# Page1.net
KiCad netlist of a schematic drawn in Altium Designer
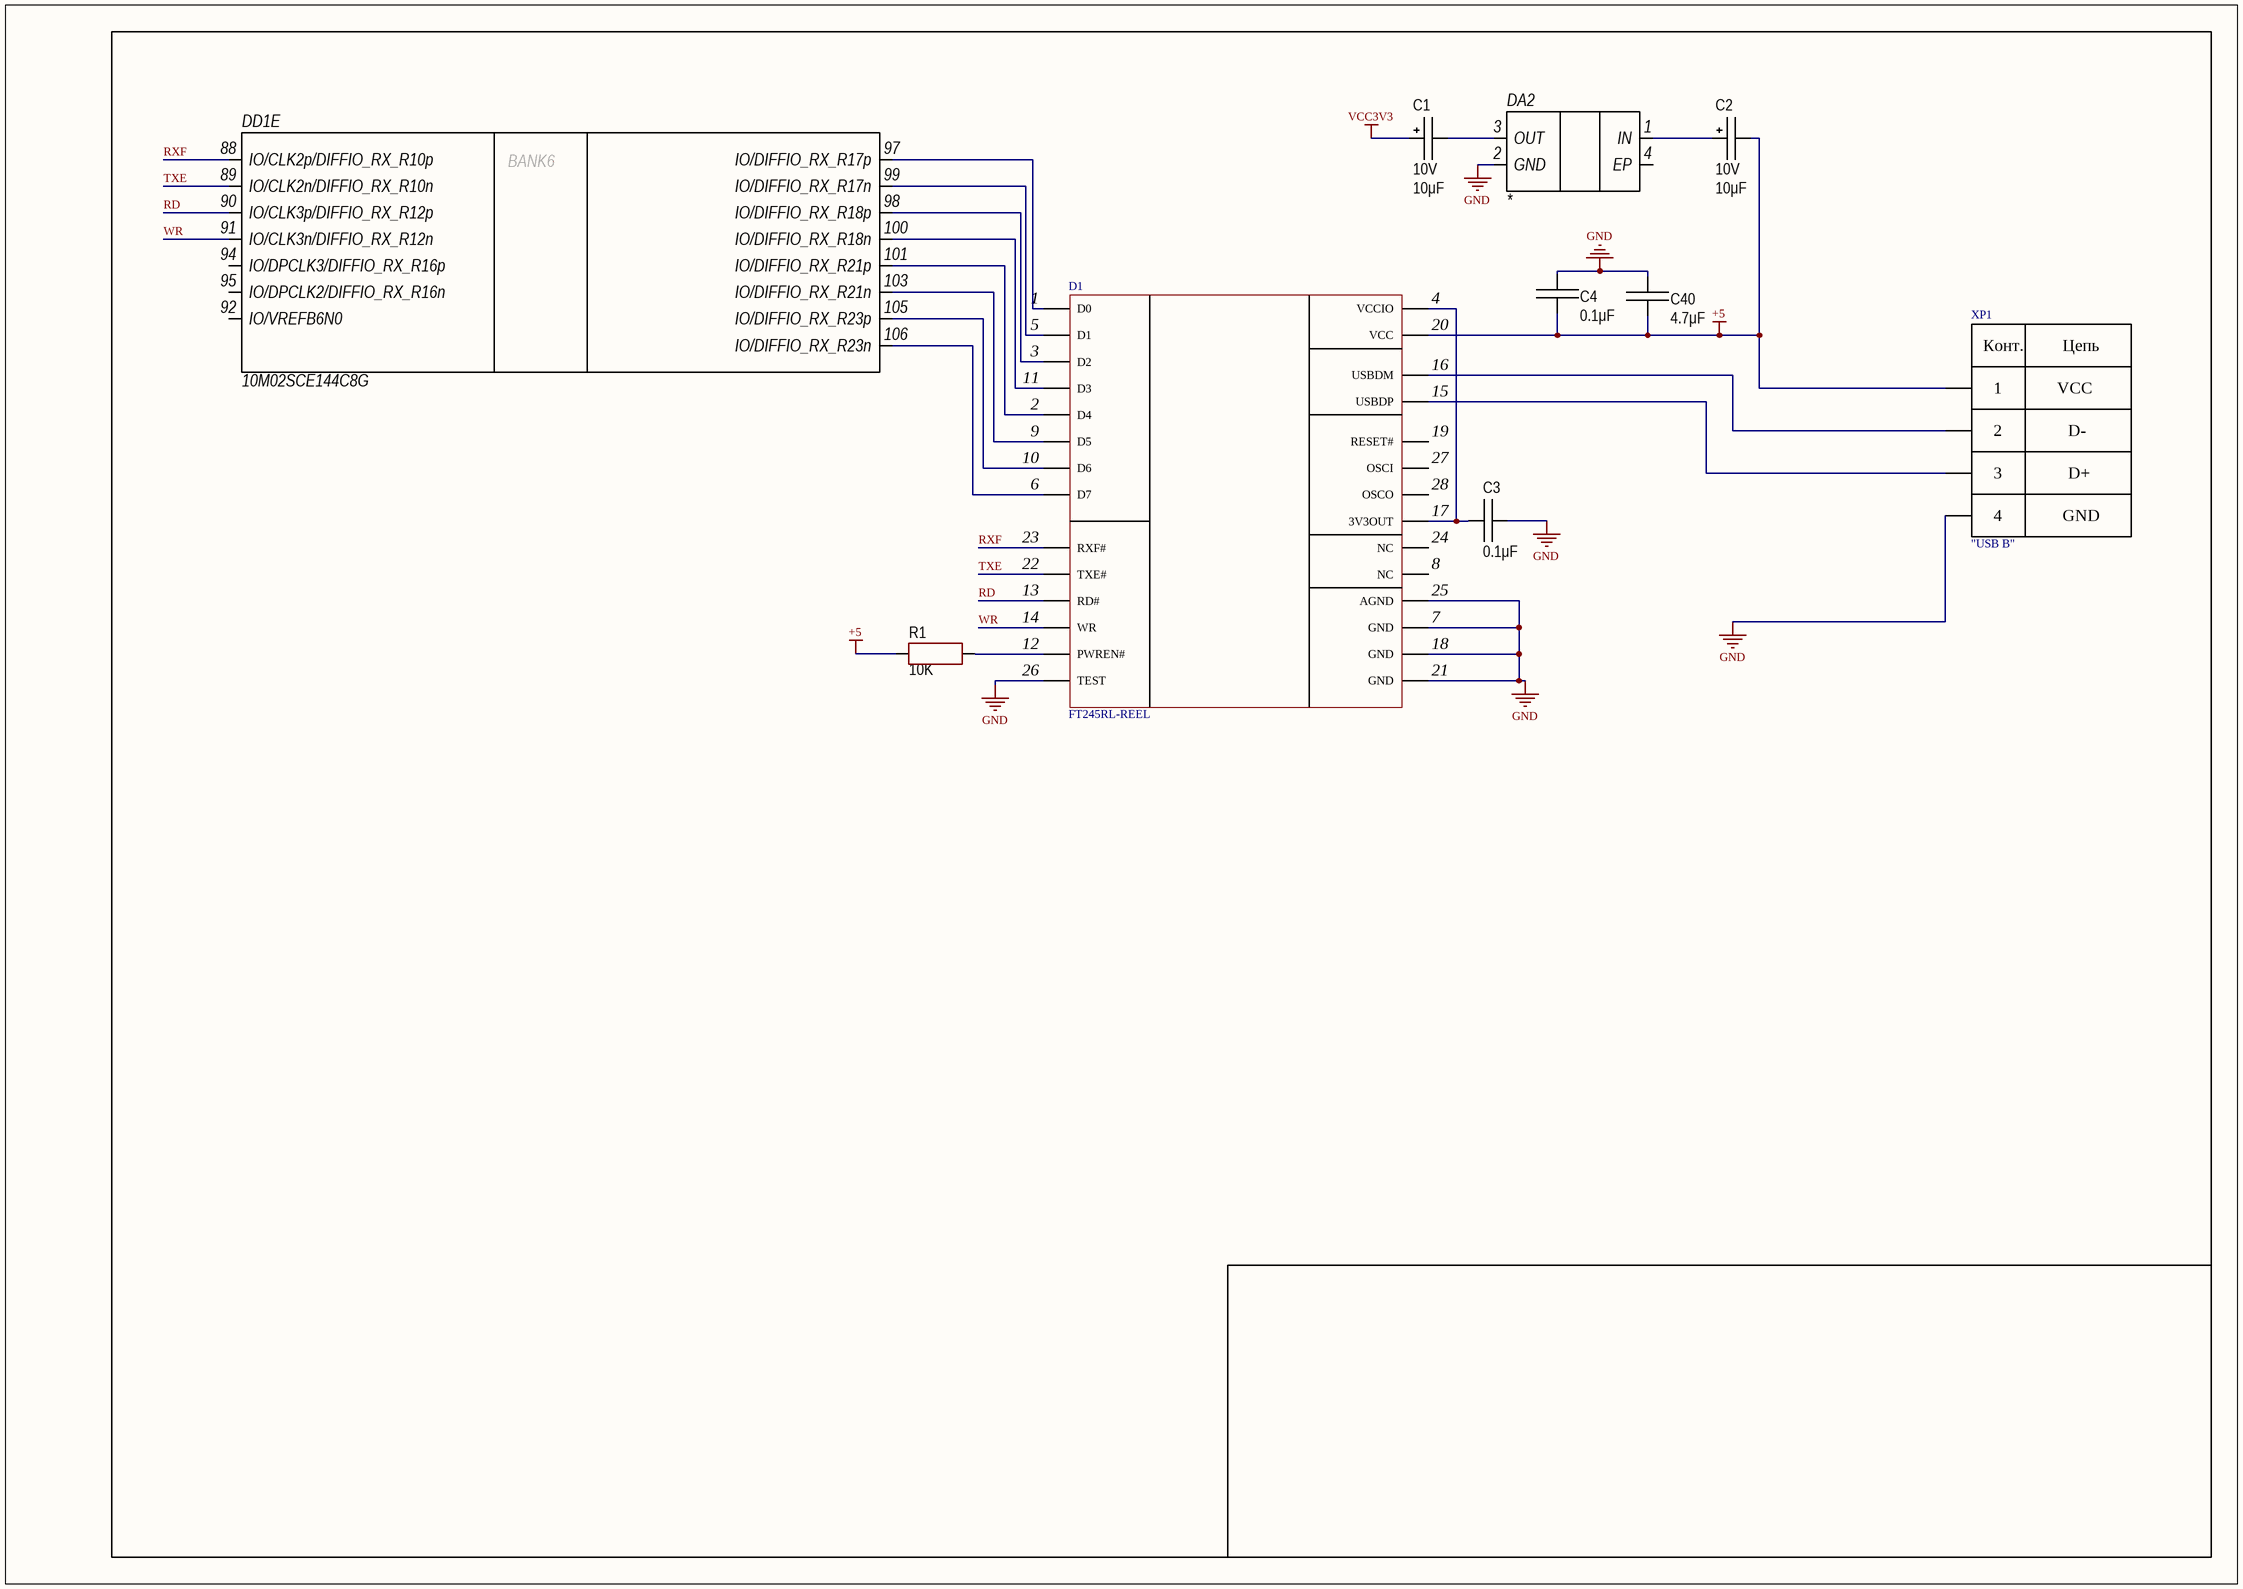
[diagram p0: Page1.SchDoc]

(export (version "E")
  (design (tool "Eeschema 10.0.6"))
  (components
    (comp (ref "C1")
      (value "10μF")
      (footprint "CAP: TANTAL-A")
      (fields
        (field (name "PARTNUMBER") "F930J107KAAAJ6")
        (field (name "VALUEMANUFACTURERPARTNUMBER") "Tantalum capacitor, 10μF, 10V, ±10%, 2Ohm, case A (3216), -55...+85°C")
        (field (name "TOLERANCE") "±10%")
        (field (name "VOLTAGE") "10V")
      )
      (libsource (lib "Capacitor") (part "Tantal_A"))
    )
    (comp (ref "C2")
      (value "10μF")
      (footprint "CAP: TANTAL-A")
      (fields
        (field (name "PARTNUMBER") "F930J107KAAAJ6")
        (field (name "VALUEMANUFACTURERPARTNUMBER") "Tantalum capacitor, 10μF, 10V, ±10%, 2Ohm, case A (3216), -55...+85°C")
        (field (name "TOLERANCE") "±10%")
        (field (name "VOLTAGE") "10V")
      )
      (libsource (lib "Capacitor") (part "Tantal_A"))
    )
    (comp (ref "C3")
      (value "0.1μF")
      (footprint "CAP: 0805")
      (fields
        (field (name "MANUFACTURER") "Yageo")
        (field (name "PARTNUMBER") "CC0805KRX7R7BB104")
        (field (name "VALUEMANUFACTURERPARTNUMBER") "Ceramic capacitor, 0.1μF, X7R, ±10%, , 0805, -55...+125°C")
      )
      (libsource (lib "Capacitor") (part "Ceramic_0805"))
    )
    (comp (ref "C4")
      (value "0.1μF")
      (footprint "CAP: 0805")
      (fields
        (field (name "MANUFACTURER") "Yageo")
        (field (name "PARTNUMBER") "CC0805KRX7R7BB104")
        (field (name "VALUEMANUFACTURERPARTNUMBER") "Ceramic capacitor, 0.1μF, X7R, ±10%, , 0805, -55...+125°C")
      )
      (libsource (lib "Capacitor") (part "Ceramic_0805"))
    )
    (comp (ref "C40")
      (value "4.7μF")
      (footprint "CAP: 0805")
      (fields
        (field (name "MANUFACTURER") "Yageo")
        (field (name "PARTNUMBER") "CC0805KRX7R7BB104")
        (field (name "VALUEMANUFACTURERPARTNUMBER") "Ceramic capacitor, 4.7μF, X7R, ±10%, , 0805, -55...+125°C")
      )
      (libsource (lib "Capacitor") (part "Ceramic_0805"))
    )
    (comp (ref "D1")
      (value "FT245RL-REEL")
      (footprint "28-SSOP")
      (description "IC USB TO PARALLEL FIFO 28-SSOP")
      (libsource (lib "Integrated_Library") (part "FT245RL-REEL"))
    )
    (comp (ref "DA2")
      (value "*")
      (footprint "SOT-223")
      (description "Voltage Regulator")
      (fields (field (name "PARTNUMBER") "MIC5233-3.3YS"))
      (libsource (lib "Integrated_Library") (part "MIC5233"))
    )
    (comp (ref "DD1")
      (value "10M02SCE144C8G")
      (footprint "144-Lead EQFP")
      (description "MAX10 FPGA")
      (fields (field (name "MANUFACTURER") "Intel"))
      (libsource (lib "Integrated_Library") (part "10M02SCE144C8G"))
    )
    (comp (ref "R1")
      (value "10K")
      (footprint "RES: 0805")
      (fields
        (field (name "MANUFACTURER") "Yageo")
        (field (name "PARTNUMBER") "RC0805JR-07100RL")
        (field (name "VALUEMANUFACTURERPARTNUMBER") "Resistor film, 10K, , 0805, 0.125W, -55...+125°C")
      )
      (libsource (lib "Resistor") (part "Resistor_0805"))
    )
    (comp (ref "XP1")
      (value "\"USB B\"")
      (footprint "USB B")
      (libsource (lib "Integrated_Library") (part "USB B"))
    )
  )
  (nets
    (net (code "1") (name "+5") (class "Default")
      (node (ref "C2") (pin "2") (pinfunction "2_2") (pintype "power_in"))
      (node (ref "C4") (pin "1") (pinfunction "1_1") (pintype "power_in"))
      (node (ref "C40") (pin "1") (pinfunction "1_1") (pintype "power_in"))
      (node (ref "D1") (pin "20") (pinfunction "VCC_20") (pintype "power_in"))
      (node (ref "R1") (pin "1") (pinfunction "1_1") (pintype "passive"))
      (node (ref "XP1") (pin "1") (pinfunction "1_1") (pintype "passive"))
    )
    (net (code "2") (name "/RD") (class "Default")
      (node (ref "D1") (pin "13") (pinfunction "RD#_13") (pintype "power_in"))
      (node (ref "DD1") (pin "90") (pinfunction "IO/CLK3p/DIFFIO_RX_R12p_90") (pintype "power_in"))
    )
    (net (code "3") (name "/RXF") (class "Default")
      (node (ref "D1") (pin "23") (pinfunction "RXF#_23") (pintype "power_in"))
      (node (ref "DD1") (pin "88") (pinfunction "IO/CLK2p/DIFFIO_RX_R10p_88") (pintype "power_in"))
    )
    (net (code "4") (name "/TXE") (class "Default")
      (node (ref "D1") (pin "22") (pinfunction "TXE#_22") (pintype "power_in"))
      (node (ref "DD1") (pin "89") (pinfunction "IO/CLK2n/DIFFIO_RX_R10n_89") (pintype "power_in"))
    )
    (net (code "5") (name "/WR") (class "Default")
      (node (ref "D1") (pin "14") (pinfunction "WR_14") (pintype "power_in"))
      (node (ref "DD1") (pin "91") (pinfunction "IO/CLK3n/DIFFIO_RX_R12n_91") (pintype "power_in"))
    )
    (net (code "6") (name "GND") (class "Default")
      (node (ref "C3") (pin "2") (pinfunction "2_2") (pintype "power_in"))
      (node (ref "C4") (pin "2") (pinfunction "2_2") (pintype "power_in"))
      (node (ref "C40") (pin "2") (pinfunction "2_2") (pintype "power_in"))
      (node (ref "D1") (pin "18") (pinfunction "GND_18") (pintype "power_in"))
      (node (ref "D1") (pin "21") (pinfunction "GND_21") (pintype "power_in"))
      (node (ref "D1") (pin "25") (pinfunction "AGND_25") (pintype "power_in"))
      (node (ref "D1") (pin "26") (pinfunction "TEST_26") (pintype "power_in"))
      (node (ref "D1") (pin "7") (pinfunction "GND_7") (pintype "power_in"))
      (node (ref "DA2") (pin "2") (pinfunction "GND_2") (pintype "power_in"))
      (node (ref "XP1") (pin "4") (pinfunction "4_4") (pintype "passive"))
    )
    (net (code "7") (name "Net-(D1-3V3OUT)") (class "Default")
      (node (ref "C3") (pin "1") (pinfunction "1_1") (pintype "power_in"))
      (node (ref "D1") (pin "17") (pinfunction "3V3OUT_17") (pintype "power_in"))
      (node (ref "D1") (pin "4") (pinfunction "VCCIO_4") (pintype "power_in"))
    )
    (net (code "8") (name "Net-(D1-D0)") (class "Default")
      (node (ref "D1") (pin "1") (pinfunction "D0_1") (pintype "power_in"))
      (node (ref "DD1") (pin "97") (pinfunction "IO/DIFFIO_RX_R17p_97") (pintype "power_in"))
    )
    (net (code "9") (name "Net-(D1-D1)") (class "Default")
      (node (ref "D1") (pin "5") (pinfunction "D1_5") (pintype "power_in"))
      (node (ref "DD1") (pin "99") (pinfunction "IO/DIFFIO_RX_R17n_99") (pintype "power_in"))
    )
    (net (code "10") (name "Net-(D1-D2)") (class "Default")
      (node (ref "D1") (pin "3") (pinfunction "D2_3") (pintype "power_in"))
      (node (ref "DD1") (pin "98") (pinfunction "IO/DIFFIO_RX_R18p_98") (pintype "power_in"))
    )
    (net (code "11") (name "Net-(D1-D3)") (class "Default")
      (node (ref "D1") (pin "11") (pinfunction "D3_11") (pintype "power_in"))
      (node (ref "DD1") (pin "100") (pinfunction "IO/DIFFIO_RX_R18n_100") (pintype "power_in"))
    )
    (net (code "12") (name "Net-(D1-D4)") (class "Default")
      (node (ref "D1") (pin "2") (pinfunction "D4_2") (pintype "power_in"))
      (node (ref "DD1") (pin "101") (pinfunction "IO/DIFFIO_RX_R21p_101") (pintype "power_in"))
    )
    (net (code "13") (name "Net-(D1-D5)") (class "Default")
      (node (ref "D1") (pin "9") (pinfunction "D5_9") (pintype "power_in"))
      (node (ref "DD1") (pin "103") (pinfunction "IO/DIFFIO_RX_R21n_103") (pintype "power_in"))
    )
    (net (code "14") (name "Net-(D1-D6)") (class "Default")
      (node (ref "D1") (pin "10") (pinfunction "D6_10") (pintype "power_in"))
      (node (ref "DD1") (pin "105") (pinfunction "IO/DIFFIO_RX_R23p_105") (pintype "power_in"))
    )
    (net (code "15") (name "Net-(D1-D7)") (class "Default")
      (node (ref "D1") (pin "6") (pinfunction "D7_6") (pintype "power_in"))
      (node (ref "DD1") (pin "106") (pinfunction "IO/DIFFIO_RX_R23n_106") (pintype "power_in"))
    )
    (net (code "16") (name "Net-(D1-PWREN#)") (class "Default")
      (node (ref "D1") (pin "12") (pinfunction "PWREN#_12") (pintype "power_in"))
      (node (ref "R1") (pin "2") (pinfunction "2_2") (pintype "passive"))
    )
    (net (code "17") (name "Net-(D1-USBDM)") (class "Default")
      (node (ref "D1") (pin "16") (pinfunction "USBDM_16") (pintype "power_in"))
      (node (ref "XP1") (pin "2") (pinfunction "2_2") (pintype "passive"))
    )
    (net (code "18") (name "Net-(D1-USBDP)") (class "Default")
      (node (ref "D1") (pin "15") (pinfunction "USBDP_15") (pintype "power_in"))
      (node (ref "XP1") (pin "3") (pinfunction "3_3") (pintype "passive"))
    )
    (net (code "19") (name "Net-(DA2-IN)") (class "Default")
      (node (ref "C2") (pin "1") (pinfunction "1_1") (pintype "power_in"))
      (node (ref "DA2") (pin "1") (pinfunction "IN_1") (pintype "power_in"))
    )
    (net (code "20") (name "Net-(DA2-OUT)") (class "Default")
      (node (ref "C1") (pin "2") (pinfunction "2_2") (pintype "power_in"))
      (node (ref "DA2") (pin "3") (pinfunction "OUT_3") (pintype "power_in"))
    )
    (net (code "21") (name "VCC3V3") (class "Default")
      (node (ref "C1") (pin "1") (pinfunction "1_1") (pintype "power_in"))
    )
    (net (code "22") (name "unconnected-(D1-NC-Pad8)") (class "Default")
      (node (ref "D1") (pin "8") (pinfunction "NC_8") (pintype "power_in"))
    )
    (net (code "23") (name "unconnected-(D1-NC-Pad24)") (class "Default")
      (node (ref "D1") (pin "24") (pinfunction "NC_24") (pintype "power_in"))
    )
    (net (code "24") (name "unconnected-(D1-OSCI-Pad27)") (class "Default")
      (node (ref "D1") (pin "27") (pinfunction "OSCI_27") (pintype "power_in"))
    )
    (net (code "25") (name "unconnected-(D1-OSCO-Pad28)") (class "Default")
      (node (ref "D1") (pin "28") (pinfunction "OSCO_28") (pintype "power_in"))
    )
    (net (code "26") (name "unconnected-(D1-RESET#-Pad19)") (class "Default")
      (node (ref "D1") (pin "19") (pinfunction "RESET#_19") (pintype "power_in"))
    )
    (net (code "27") (name "unconnected-(DA2-EP-Pad4)") (class "Default")
      (node (ref "DA2") (pin "4") (pinfunction "EP_4") (pintype "power_in"))
    )
    (net (code "28") (name "unconnected-(DD1E-IO{slash}DPCLK2{slash}DIFFIO_RX_R16n-Pad95)") (class "Default")
      (node (ref "DD1") (pin "95") (pinfunction "IO/DPCLK2/DIFFIO_RX_R16n_95") (pintype "power_in"))
    )
    (net (code "29") (name "unconnected-(DD1E-IO{slash}DPCLK3{slash}DIFFIO_RX_R16p-Pad94)") (class "Default")
      (node (ref "DD1") (pin "94") (pinfunction "IO/DPCLK3/DIFFIO_RX_R16p_94") (pintype "power_in"))
    )
    (net (code "30") (name "unconnected-(DD1E-IO{slash}VREFB6N0-Pad92)") (class "Default")
      (node (ref "DD1") (pin "92") (pinfunction "IO/VREFB6N0_92") (pintype "power_in"))
    )
  )
)
